# DrizzlingBytes.net
KiCad netlist of a schematic drawn in EAGLE
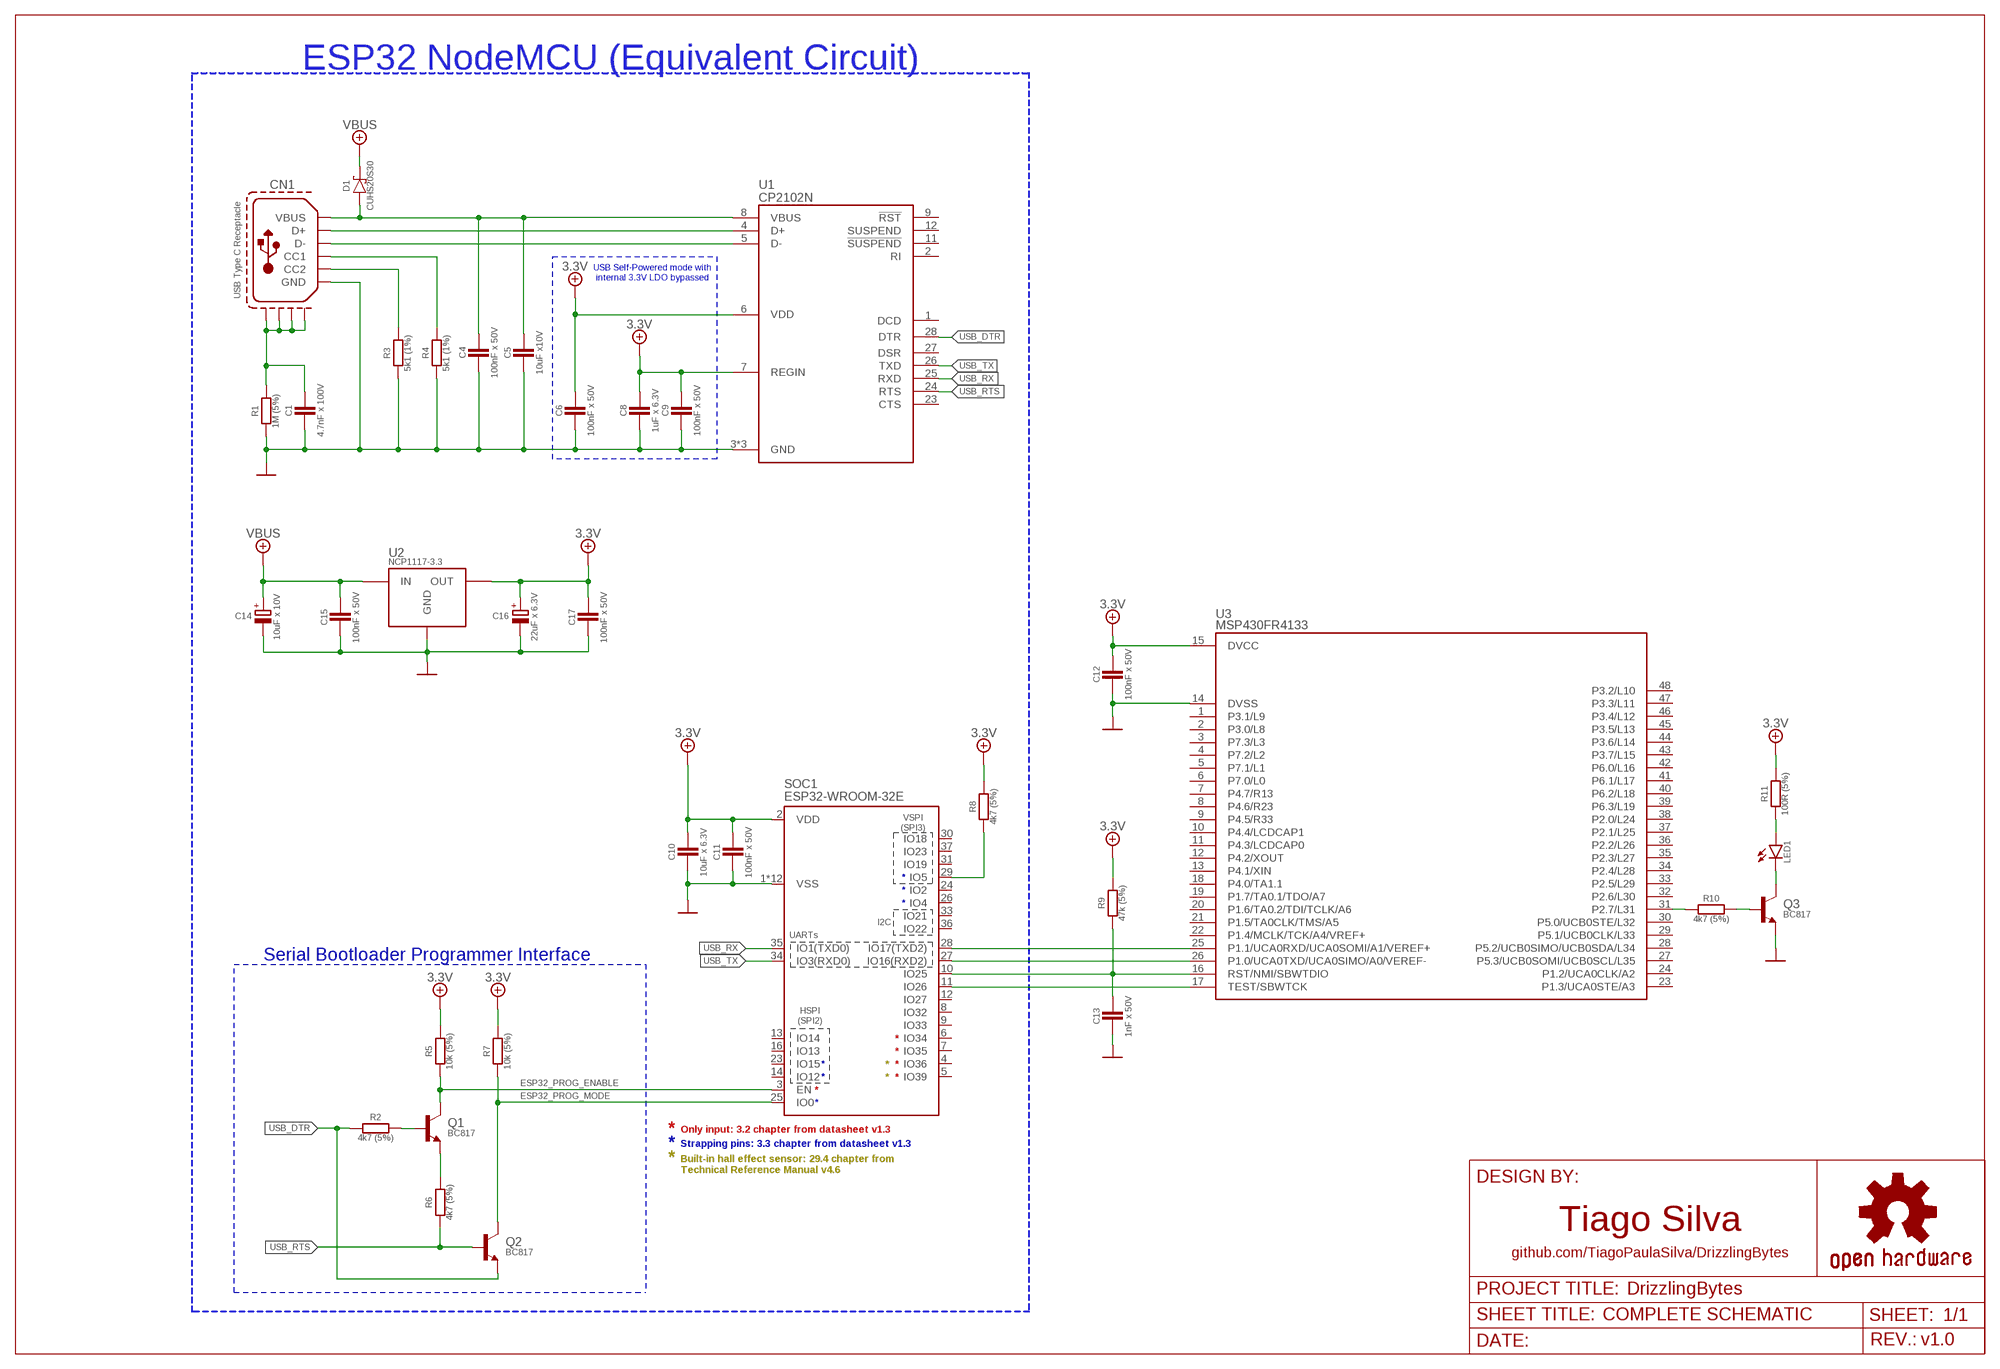
[diagram p0: schematic, sheet 1]

(export (version "E")
  (design (tool "Eeschema 10.0.6"))
  (components
    (comp (ref "C1")
      (value "4.7nF x 100V")
      (footprint "eagle-import:C0402")
      (libsource (lib "eagle-import") (part "C_0402"))
    )
    (comp (ref "C4")
      (value "100nF x 50V")
      (footprint "eagle-import:C0402")
      (libsource (lib "eagle-import") (part "C_0402"))
    )
    (comp (ref "C5")
      (value "10uF x10V")
      (footprint "eagle-import:C0402")
      (libsource (lib "eagle-import") (part "C_0402"))
    )
    (comp (ref "C6")
      (value "100nF x 50V")
      (footprint "eagle-import:C0402")
      (libsource (lib "eagle-import") (part "C_0402"))
    )
    (comp (ref "C8")
      (value "1uF x 6.3V")
      (footprint "eagle-import:C0402")
      (libsource (lib "eagle-import") (part "C_0402"))
    )
    (comp (ref "C9")
      (value "100nF x 50V")
      (footprint "eagle-import:C0402")
      (libsource (lib "eagle-import") (part "C_0402"))
    )
    (comp (ref "C10")
      (value "10uF x 6.3V")
      (footprint "eagle-import:C0402")
      (libsource (lib "eagle-import") (part "C_0402"))
    )
    (comp (ref "C11")
      (value "100nF x 50V")
      (footprint "eagle-import:C0402")
      (libsource (lib "eagle-import") (part "C_0402"))
    )
    (comp (ref "C12")
      (value "100nF x 50V")
      (footprint "eagle-import:C0402")
      (libsource (lib "eagle-import") (part "C_0402"))
    )
    (comp (ref "C13")
      (value "1nF x 50V")
      (footprint "eagle-import:C0402")
      (libsource (lib "eagle-import") (part "C_0402"))
    )
    (comp (ref "C14")
      (value "10uF x 10V")
      (footprint "eagle-import:C1206_POL")
      (description "Tantalum Electrolytic Capacitors (Low ESR)")
      (libsource (lib "eagle-import") (part "CP_1206_POL"))
    )
    (comp (ref "C15")
      (value "100nF x 50V")
      (footprint "eagle-import:C0402")
      (libsource (lib "eagle-import") (part "C_0402"))
    )
    (comp (ref "C16")
      (value "22uF x 6.3V")
      (footprint "eagle-import:C1206_POL")
      (description "Tantalum Electrolytic Capacitors (Low ESR)")
      (libsource (lib "eagle-import") (part "CP_1206_POL"))
    )
    (comp (ref "C17")
      (value "100nF x 50V")
      (footprint "eagle-import:C0402")
      (libsource (lib "eagle-import") (part "C_0402"))
    )
    (comp (ref "CN1")
      (value "USB Type C Receptacle")
      (footprint "eagle-import:USB-C-16P-2LAYER-PADS")
      (libsource (lib "eagle-import") (part "USB-C-16P-2LAYERS"))
    )
    (comp (ref "D1")
      (value "SCHOTTKY-CUHS20S30")
      (footprint "eagle-import:US2H-2")
      (fields (field (name "FAMILY") "CUHS20S30"))
      (libsource (lib "eagle-import") (part "SCHOTTKY-CUHS20S30"))
    )
    (comp (ref "LED1")
      (value "LED-0402")
      (footprint "eagle-import:LED-0402")
      (libsource (lib "eagle-import") (part "LED-0402"))
    )
    (comp (ref "Q1")
      (value "NPN-BC817")
      (footprint "eagle-import:SOT23-3")
      (fields (field (name "FAMILY") "BC817"))
      (libsource (lib "eagle-import") (part "NPN-BC817"))
    )
    (comp (ref "Q2")
      (value "NPN-BC817")
      (footprint "eagle-import:SOT23-3")
      (fields (field (name "FAMILY") "BC817"))
      (libsource (lib "eagle-import") (part "NPN-BC817"))
    )
    (comp (ref "Q3")
      (value "NPN-BC817")
      (footprint "eagle-import:SOT23-3")
      (fields (field (name "FAMILY") "BC817"))
      (libsource (lib "eagle-import") (part "NPN-BC817"))
    )
    (comp (ref "R1")
      (value "1M (5%)")
      (footprint "eagle-import:R0402")
      (libsource (lib "eagle-import") (part "R_0402"))
    )
    (comp (ref "R2")
      (value "4k7 (5%)")
      (footprint "eagle-import:R0402")
      (libsource (lib "eagle-import") (part "R_0402"))
    )
    (comp (ref "R3")
      (value "5k1 (1%)")
      (footprint "eagle-import:R0402")
      (libsource (lib "eagle-import") (part "R_0402"))
    )
    (comp (ref "R4")
      (value "5k1 (1%)")
      (footprint "eagle-import:R0402")
      (libsource (lib "eagle-import") (part "R_0402"))
    )
    (comp (ref "R5")
      (value "10k (5%)")
      (footprint "eagle-import:R0402")
      (libsource (lib "eagle-import") (part "R_0402"))
    )
    (comp (ref "R6")
      (value "4k7 (5%)")
      (footprint "eagle-import:R0402")
      (libsource (lib "eagle-import") (part "R_0402"))
    )
    (comp (ref "R7")
      (value "10k (5%)")
      (footprint "eagle-import:R0402")
      (libsource (lib "eagle-import") (part "R_0402"))
    )
    (comp (ref "R8")
      (value "4k7 (5%)")
      (footprint "eagle-import:R0402")
      (libsource (lib "eagle-import") (part "R_0402"))
    )
    (comp (ref "R9")
      (value "47k (5%)")
      (footprint "eagle-import:R0402")
      (libsource (lib "eagle-import") (part "R_0402"))
    )
    (comp (ref "R10")
      (value "4k7 (5%)")
      (footprint "eagle-import:R0402")
      (libsource (lib "eagle-import") (part "R_0402"))
    )
    (comp (ref "R11")
      (value "100R (5%)")
      (footprint "eagle-import:R0402")
      (libsource (lib "eagle-import") (part "R_0402"))
    )
    (comp (ref "SOC1")
      (value "ESP32-WROOM-32E")
      (footprint "eagle-import:ESP32-WROOM-32E")
      (libsource (lib "eagle-import") (part "ESP32-WROOM-32E-N4"))
    )
    (comp (ref "U1")
      (value "CP2102N")
      (footprint "eagle-import:QFN-28")
      (libsource (lib "eagle-import") (part "CP2102N"))
    )
    (comp (ref "U2")
      (value "1117-3.3V")
      (footprint "eagle-import:SOT-223-3")
      (fields (field (name "FAMILY") "LT1117-3.3") (field (name "FAMILY_1") "NCP1117-3.3"))
      (libsource (lib "eagle-import") (part "1117-3.3V"))
    )
    (comp (ref "U3")
      (value "MSP430FR4133")
      (footprint "eagle-import:TSSOP-48")
      (fields
        (field (name "MANUFACTURER_PART_NUMBER") "MSP430FR4133IG48R")
        (field (name "MOUSER_PART_NUMBER") "595-MSP430R4133IG48R")
      )
      (libsource (lib "eagle-import") (part "MSP430FR4133IG48R"))
    )
  )
  (nets
    (net (code "1") (name "/ESP32_PROG_ENABLE") (class "Default")
      (node (ref "Q1") (pin "3") (pinfunction "C_3") (pintype "passive"))
      (node (ref "R5") (pin "2") (pinfunction "2_2") (pintype "passive"))
      (node (ref "SOC1") (pin "3") (pinfunction "EN_3") (pintype "input"))
    )
    (net (code "2") (name "/ESP32_PROG_MODE") (class "Default")
      (node (ref "Q2") (pin "3") (pinfunction "C_3") (pintype "passive"))
      (node (ref "R7") (pin "2") (pinfunction "2_2") (pintype "passive"))
      (node (ref "SOC1") (pin "25") (pinfunction "IO0_25") (pintype "bidirectional"))
    )
    (net (code "3") (name "0V") (class "Default")
      (node (ref "C1") (pin "1") (pinfunction "1_1") (pintype "passive"))
      (node (ref "C10") (pin "2") (pinfunction "2_2") (pintype "passive"))
      (node (ref "C11") (pin "2") (pinfunction "2_2") (pintype "passive"))
      (node (ref "C12") (pin "1") (pinfunction "1_1") (pintype "passive"))
      (node (ref "C13") (pin "2") (pinfunction "2_2") (pintype "passive"))
      (node (ref "C14") (pin "2") (pinfunction "-_2") (pintype "passive"))
      (node (ref "C15") (pin "2") (pinfunction "2_2") (pintype "passive"))
      (node (ref "C16") (pin "2") (pinfunction "-_2") (pintype "passive"))
      (node (ref "C17") (pin "2") (pinfunction "2_2") (pintype "passive"))
      (node (ref "C4") (pin "1") (pinfunction "1_1") (pintype "passive"))
      (node (ref "C5") (pin "1") (pinfunction "1_1") (pintype "passive"))
      (node (ref "C6") (pin "1") (pinfunction "1_1") (pintype "passive"))
      (node (ref "C8") (pin "1") (pinfunction "1_1") (pintype "passive"))
      (node (ref "C9") (pin "1") (pinfunction "1_1") (pintype "passive"))
      (node (ref "CN1") (pin "GND") (pinfunction "GND_GND") (pintype "bidirectional"))
      (node (ref "CN1") (pin "GND2") (pinfunction "GND_GND2") (pintype "bidirectional"))
      (node (ref "Q3") (pin "2") (pinfunction "E_2") (pintype "passive"))
      (node (ref "R1") (pin "2") (pinfunction "2_2") (pintype "passive"))
      (node (ref "R3") (pin "2") (pinfunction "2_2") (pintype "passive"))
      (node (ref "R4") (pin "2") (pinfunction "2_2") (pintype "passive"))
      (node (ref "SOC1") (pin "1") (pinfunction "VSS_1") (pintype "power_in"))
      (node (ref "SOC1") (pin "15") (pinfunction "VSS_15") (pintype "power_in"))
      (node (ref "SOC1") (pin "38") (pinfunction "VSS_38") (pintype "power_in"))
      (node (ref "SOC1") (pin "E1") (pinfunction "VSS_E1") (pintype "power_in"))
      (node (ref "SOC1") (pin "E2") (pinfunction "VSS_E2") (pintype "power_in"))
      (node (ref "SOC1") (pin "E3") (pinfunction "VSS_E3") (pintype "power_in"))
      (node (ref "SOC1") (pin "E4") (pinfunction "VSS_E4") (pintype "power_in"))
      (node (ref "SOC1") (pin "E5") (pinfunction "VSS_E5") (pintype "power_in"))
      (node (ref "SOC1") (pin "E6") (pinfunction "VSS_E6") (pintype "power_in"))
      (node (ref "SOC1") (pin "E7") (pinfunction "VSS_E7") (pintype "power_in"))
      (node (ref "SOC1") (pin "E8") (pinfunction "VSS_E8") (pintype "power_in"))
      (node (ref "SOC1") (pin "E9") (pinfunction "VSS_E9") (pintype "power_in"))
      (node (ref "U1") (pin "3") (pinfunction "GND_3") (pintype "power_in"))
      (node (ref "U1") (pin "EXP") (pinfunction "GND_EXP") (pintype "power_in"))
      (node (ref "U1") (pin "M") (pinfunction "GND_M") (pintype "power_in"))
      (node (ref "U2") (pin "1") (pinfunction "GND_1") (pintype "bidirectional"))
      (node (ref "U3") (pin "14") (pinfunction "DVSS_14") (pintype "bidirectional"))
    )
    (net (code "4") (name "3.3V") (class "Default")
      (node (ref "C10") (pin "1") (pinfunction "1_1") (pintype "passive"))
      (node (ref "C11") (pin "1") (pinfunction "1_1") (pintype "passive"))
      (node (ref "C12") (pin "2") (pinfunction "2_2") (pintype "passive"))
      (node (ref "C16") (pin "1") (pinfunction "+_1") (pintype "passive"))
      (node (ref "C17") (pin "1") (pinfunction "1_1") (pintype "passive"))
      (node (ref "C6") (pin "2") (pinfunction "2_2") (pintype "passive"))
      (node (ref "C8") (pin "2") (pinfunction "2_2") (pintype "passive"))
      (node (ref "C9") (pin "2") (pinfunction "2_2") (pintype "passive"))
      (node (ref "R11") (pin "2") (pinfunction "2_2") (pintype "passive"))
      (node (ref "R5") (pin "1") (pinfunction "1_1") (pintype "passive"))
      (node (ref "R7") (pin "1") (pinfunction "1_1") (pintype "passive"))
      (node (ref "R8") (pin "2") (pinfunction "2_2") (pintype "passive"))
      (node (ref "R9") (pin "2") (pinfunction "2_2") (pintype "passive"))
      (node (ref "SOC1") (pin "2") (pinfunction "VDD_2") (pintype "power_in"))
      (node (ref "U1") (pin "6") (pinfunction "VDD_6") (pintype "power_in"))
      (node (ref "U1") (pin "7") (pinfunction "REGIN_7") (pintype "passive"))
      (node (ref "U2") (pin "2") (pinfunction "OUT_2") (pintype "bidirectional"))
      (node (ref "U2") (pin "4") (pinfunction "OUT_4") (pintype "bidirectional"))
      (node (ref "U3") (pin "15") (pinfunction "DVCC_15") (pintype "bidirectional"))
    )
    (net (code "5") (name "Net-(CN1-CC1)") (class "Default")
      (node (ref "CN1") (pin "A5") (pinfunction "CC1_A5") (pintype "bidirectional"))
      (node (ref "R4") (pin "1") (pinfunction "1_1") (pintype "passive"))
    )
    (net (code "6") (name "Net-(CN1-CC2)") (class "Default")
      (node (ref "CN1") (pin "B5") (pinfunction "CC2_B5") (pintype "bidirectional"))
      (node (ref "R3") (pin "1") (pinfunction "1_1") (pintype "passive"))
    )
    (net (code "7") (name "Net-(CN1-S1)") (class "Default")
      (node (ref "C1") (pin "2") (pinfunction "2_2") (pintype "passive"))
      (node (ref "CN1") (pin "SHLD1") (pinfunction "S1_SHLD1") (pintype "passive"))
      (node (ref "CN1") (pin "SHLD2") (pinfunction "S2_SHLD2") (pintype "passive"))
      (node (ref "CN1") (pin "SHLD3") (pinfunction "S3_SHLD3") (pintype "passive"))
      (node (ref "CN1") (pin "SHLD4") (pinfunction "S4_SHLD4") (pintype "passive"))
      (node (ref "R1") (pin "1") (pinfunction "1_1") (pintype "passive"))
    )
    (net (code "8") (name "Net-(D1-A)") (class "Default")
      (node (ref "C4") (pin "2") (pinfunction "2_2") (pintype "passive"))
      (node (ref "C5") (pin "2") (pinfunction "2_2") (pintype "passive"))
      (node (ref "CN1") (pin "VBUS1") (pinfunction "VBUS_VBUS1") (pintype "bidirectional"))
      (node (ref "CN1") (pin "VBUS2") (pinfunction "VBUS_VBUS2") (pintype "bidirectional"))
      (node (ref "D1") (pin "2") (pinfunction "A_2") (pintype "passive"))
      (node (ref "U1") (pin "8") (pinfunction "VBUS_8") (pintype "passive"))
    )
    (net (code "9") (name "Net-(LED1-A)") (class "Default")
      (node (ref "LED1") (pin "2") (pinfunction "A_2") (pintype "passive"))
      (node (ref "R11") (pin "1") (pinfunction "1_1") (pintype "passive"))
    )
    (net (code "10") (name "Net-(LED1-K)") (class "Default")
      (node (ref "LED1") (pin "1") (pinfunction "K_1") (pintype "passive"))
      (node (ref "Q3") (pin "3") (pinfunction "C_3") (pintype "passive"))
    )
    (net (code "11") (name "Net-(Q1-B)") (class "Default")
      (node (ref "Q1") (pin "1") (pinfunction "B_1") (pintype "passive"))
      (node (ref "R2") (pin "1") (pinfunction "1_1") (pintype "passive"))
    )
    (net (code "12") (name "Net-(Q3-B)") (class "Default")
      (node (ref "Q3") (pin "1") (pinfunction "B_1") (pintype "passive"))
      (node (ref "R10") (pin "2") (pinfunction "2_2") (pintype "passive"))
    )
    (net (code "13") (name "Net-(SOC1-IO5)") (class "Default")
      (node (ref "R8") (pin "1") (pinfunction "1_1") (pintype "passive"))
      (node (ref "SOC1") (pin "29") (pinfunction "IO5_29") (pintype "bidirectional"))
    )
    (net (code "14") (name "Net-(SOC1-IO16(RXD2))") (class "Default")
      (node (ref "SOC1") (pin "27") (pinfunction "IO16(RXD2)_27") (pintype "bidirectional"))
      (node (ref "U3") (pin "26") (pinfunction "P1.0/UCA0TXD/UCA0SIMO/A0/VEREF-_26") (pintype "bidirectional"))
    )
    (net (code "15") (name "Net-(SOC1-IO17(TXD2))") (class "Default")
      (node (ref "SOC1") (pin "28") (pinfunction "IO17(TXD2)_28") (pintype "bidirectional"))
      (node (ref "U3") (pin "25") (pinfunction "P1.1/UCA0RXD/UCA0SOMI/A1/VEREF+_25") (pintype "bidirectional"))
    )
    (net (code "16") (name "Net-(SOC1-IO25)") (class "Default")
      (node (ref "C13") (pin "1") (pinfunction "1_1") (pintype "passive"))
      (node (ref "R9") (pin "1") (pinfunction "1_1") (pintype "passive"))
      (node (ref "SOC1") (pin "10") (pinfunction "IO25_10") (pintype "bidirectional"))
      (node (ref "U3") (pin "16") (pinfunction "RST/NMI/SBWTDIO_16") (pintype "bidirectional"))
    )
    (net (code "17") (name "Net-(SOC1-IO26)") (class "Default")
      (node (ref "SOC1") (pin "11") (pinfunction "IO26_11") (pintype "bidirectional"))
      (node (ref "U3") (pin "17") (pinfunction "TEST/SBWTCK_17") (pintype "bidirectional"))
    )
    (net (code "18") (name "Net-(U1-D+)") (class "Default")
      (node (ref "CN1") (pin "A6") (pinfunction "D+_A6") (pintype "bidirectional"))
      (node (ref "CN1") (pin "B6") (pinfunction "D+_B6") (pintype "bidirectional"))
      (node (ref "U1") (pin "4") (pinfunction "D+_4") (pintype "bidirectional"))
    )
    (net (code "19") (name "Net-(U1-D-)") (class "Default")
      (node (ref "CN1") (pin "A7") (pinfunction "D-_A7") (pintype "bidirectional"))
      (node (ref "CN1") (pin "B7") (pinfunction "D-_B7") (pintype "bidirectional"))
      (node (ref "U1") (pin "5") (pinfunction "D-_5") (pintype "bidirectional"))
    )
    (net (code "20") (name "Net-(U3-P2.7{slash}L31)") (class "Default")
      (node (ref "R10") (pin "1") (pinfunction "1_1") (pintype "passive"))
      (node (ref "U3") (pin "31") (pinfunction "P2.7/L31_31") (pintype "bidirectional"))
    )
    (net (code "21") (name "USB_DTR") (class "Default")
      (node (ref "Q2") (pin "2") (pinfunction "E_2") (pintype "passive"))
      (node (ref "R2") (pin "2") (pinfunction "2_2") (pintype "passive"))
      (node (ref "U1") (pin "28") (pinfunction "DTR_28") (pintype "output"))
    )
    (net (code "22") (name "USB_RTS") (class "Default")
      (node (ref "Q1") (pin "2") (pinfunction "E_2") (pintype "passive"))
      (node (ref "Q2") (pin "1") (pinfunction "B_1") (pintype "passive"))
      (node (ref "R6") (pin "1") (pinfunction "1_1") (pintype "passive"))
      (node (ref "R6") (pin "2") (pinfunction "2_2") (pintype "passive"))
      (node (ref "U1") (pin "24") (pinfunction "RTS_24") (pintype "output"))
    )
    (net (code "23") (name "USB_RX") (class "Default")
      (node (ref "SOC1") (pin "35") (pinfunction "IO1(TXD0)_35") (pintype "bidirectional"))
      (node (ref "U1") (pin "25") (pinfunction "RXD_25") (pintype "input"))
    )
    (net (code "24") (name "USB_TX") (class "Default")
      (node (ref "SOC1") (pin "34") (pinfunction "IO3(RXD0)_34") (pintype "bidirectional"))
      (node (ref "U1") (pin "26") (pinfunction "TXD_26") (pintype "output"))
    )
    (net (code "25") (name "VBUS") (class "Default")
      (node (ref "C14") (pin "1") (pinfunction "+_1") (pintype "passive"))
      (node (ref "C15") (pin "1") (pinfunction "1_1") (pintype "passive"))
      (node (ref "D1") (pin "1") (pinfunction "K_1") (pintype "passive"))
      (node (ref "U2") (pin "3") (pinfunction "IN_3") (pintype "bidirectional"))
    )
    (net (code "26") (name "unconnected-(SOC1-IO2-Pad24)") (class "Default")
      (node (ref "SOC1") (pin "24") (pinfunction "IO2_24") (pintype "bidirectional"))
    )
    (net (code "27") (name "unconnected-(SOC1-IO4-Pad26)") (class "Default")
      (node (ref "SOC1") (pin "26") (pinfunction "IO4_26") (pintype "bidirectional"))
    )
    (net (code "28") (name "unconnected-(SOC1-IO12-Pad14)") (class "Default")
      (node (ref "SOC1") (pin "14") (pinfunction "IO12_14") (pintype "bidirectional"))
    )
    (net (code "29") (name "unconnected-(SOC1-IO13-Pad16)") (class "Default")
      (node (ref "SOC1") (pin "16") (pinfunction "IO13_16") (pintype "bidirectional"))
    )
    (net (code "30") (name "unconnected-(SOC1-IO14-Pad13)") (class "Default")
      (node (ref "SOC1") (pin "13") (pinfunction "IO14_13") (pintype "bidirectional"))
    )
    (net (code "31") (name "unconnected-(SOC1-IO15-Pad23)") (class "Default")
      (node (ref "SOC1") (pin "23") (pinfunction "IO15_23") (pintype "bidirectional"))
    )
    (net (code "32") (name "unconnected-(SOC1-IO18-Pad30)") (class "Default")
      (node (ref "SOC1") (pin "30") (pinfunction "IO18_30") (pintype "bidirectional"))
    )
    (net (code "33") (name "unconnected-(SOC1-IO19-Pad31)") (class "Default")
      (node (ref "SOC1") (pin "31") (pinfunction "IO19_31") (pintype "bidirectional"))
    )
    (net (code "34") (name "unconnected-(SOC1-IO21-Pad33)") (class "Default")
      (node (ref "SOC1") (pin "33") (pinfunction "IO21_33") (pintype "bidirectional"))
    )
    (net (code "35") (name "unconnected-(SOC1-IO22-Pad36)") (class "Default")
      (node (ref "SOC1") (pin "36") (pinfunction "IO22_36") (pintype "bidirectional"))
    )
    (net (code "36") (name "unconnected-(SOC1-IO23-Pad37)") (class "Default")
      (node (ref "SOC1") (pin "37") (pinfunction "IO23_37") (pintype "bidirectional"))
    )
    (net (code "37") (name "unconnected-(SOC1-IO27-Pad12)") (class "Default")
      (node (ref "SOC1") (pin "12") (pinfunction "IO27_12") (pintype "bidirectional"))
    )
    (net (code "38") (name "unconnected-(SOC1-IO32-Pad8)") (class "Default")
      (node (ref "SOC1") (pin "8") (pinfunction "IO32_8") (pintype "bidirectional"))
    )
    (net (code "39") (name "unconnected-(SOC1-IO33-Pad9)") (class "Default")
      (node (ref "SOC1") (pin "9") (pinfunction "IO33_9") (pintype "bidirectional"))
    )
    (net (code "40") (name "unconnected-(SOC1-IO34-Pad6)") (class "Default")
      (node (ref "SOC1") (pin "6") (pinfunction "IO34_6") (pintype "bidirectional"))
    )
    (net (code "41") (name "unconnected-(SOC1-IO35-Pad7)") (class "Default")
      (node (ref "SOC1") (pin "7") (pinfunction "IO35_7") (pintype "bidirectional"))
    )
    (net (code "42") (name "unconnected-(SOC1-IO36-Pad4)") (class "Default")
      (node (ref "SOC1") (pin "4") (pinfunction "IO36_4") (pintype "bidirectional"))
    )
    (net (code "43") (name "unconnected-(SOC1-IO39-Pad5)") (class "Default")
      (node (ref "SOC1") (pin "5") (pinfunction "IO39_5") (pintype "bidirectional"))
    )
    (net (code "44") (name "unconnected-(U1-CTS-Pad23)") (class "Default")
      (node (ref "U1") (pin "23") (pinfunction "CTS_23") (pintype "passive"))
    )
    (net (code "45") (name "unconnected-(U1-DCD-Pad1)") (class "Default")
      (node (ref "U1") (pin "1") (pinfunction "DCD_1") (pintype "passive"))
    )
    (net (code "46") (name "unconnected-(U1-DSR-Pad27)") (class "Default")
      (node (ref "U1") (pin "27") (pinfunction "DSR_27") (pintype "passive"))
    )
    (net (code "47") (name "unconnected-(U1-RI-Pad2)") (class "Default")
      (node (ref "U1") (pin "2") (pinfunction "RI_2") (pintype "passive"))
    )
    (net (code "48") (name "unconnected-(U1-SUSPEND-Pad12)") (class "Default")
      (node (ref "U1") (pin "12") (pinfunction "SUSPEND_12") (pintype "passive"))
    )
    (net (code "49") (name "unconnected-(U1-~{RST}-Pad9)") (class "Default")
      (node (ref "U1") (pin "9") (pinfunction "~{RST}_9") (pintype "bidirectional"))
    )
    (net (code "50") (name "unconnected-(U1-~{SUSPEND}-Pad11)") (class "Default")
      (node (ref "U1") (pin "11") (pinfunction "~{SUSPEND}_11") (pintype "output"))
    )
    (net (code "51") (name "unconnected-(U3-P1.2{slash}UCA0CLK{slash}A2-Pad24)") (class "Default")
      (node (ref "U3") (pin "24") (pinfunction "P1.2/UCA0CLK/A2_24") (pintype "bidirectional"))
    )
    (net (code "52") (name "unconnected-(U3-P1.3{slash}UCA0STE{slash}A3-Pad23)") (class "Default")
      (node (ref "U3") (pin "23") (pinfunction "P1.3/UCA0STE/A3_23") (pintype "bidirectional"))
    )
    (net (code "53") (name "unconnected-(U3-P1.4{slash}MCLK{slash}TCK{slash}A4{slash}VREF+-Pad22)") (class "Default")
      (node (ref "U3") (pin "22") (pinfunction "P1.4/MCLK/TCK/A4/VREF+_22") (pintype "bidirectional"))
    )
    (net (code "54") (name "unconnected-(U3-P1.5{slash}TA0CLK{slash}TMS{slash}A5-Pad21)") (class "Default")
      (node (ref "U3") (pin "21") (pinfunction "P1.5/TA0CLK/TMS/A5_21") (pintype "bidirectional"))
    )
    (net (code "55") (name "unconnected-(U3-P1.6{slash}TA0.2{slash}TDI{slash}TCLK{slash}A6-Pad20)") (class "Default")
      (node (ref "U3") (pin "20") (pinfunction "P1.6/TA0.2/TDI/TCLK/A6_20") (pintype "bidirectional"))
    )
    (net (code "56") (name "unconnected-(U3-P1.7{slash}TA0.1{slash}TDO{slash}A7-Pad19)") (class "Default")
      (node (ref "U3") (pin "19") (pinfunction "P1.7/TA0.1/TDO/A7_19") (pintype "bidirectional"))
    )
    (net (code "57") (name "unconnected-(U3-P2.0{slash}L24-Pad38)") (class "Default")
      (node (ref "U3") (pin "38") (pinfunction "P2.0/L24_38") (pintype "bidirectional"))
    )
    (net (code "58") (name "unconnected-(U3-P2.1{slash}L25-Pad37)") (class "Default")
      (node (ref "U3") (pin "37") (pinfunction "P2.1/L25_37") (pintype "bidirectional"))
    )
    (net (code "59") (name "unconnected-(U3-P2.2{slash}L26-Pad36)") (class "Default")
      (node (ref "U3") (pin "36") (pinfunction "P2.2/L26_36") (pintype "bidirectional"))
    )
    (net (code "60") (name "unconnected-(U3-P2.3{slash}L27-Pad35)") (class "Default")
      (node (ref "U3") (pin "35") (pinfunction "P2.3/L27_35") (pintype "bidirectional"))
    )
    (net (code "61") (name "unconnected-(U3-P2.4{slash}L28-Pad34)") (class "Default")
      (node (ref "U3") (pin "34") (pinfunction "P2.4/L28_34") (pintype "bidirectional"))
    )
    (net (code "62") (name "unconnected-(U3-P2.5{slash}L29-Pad33)") (class "Default")
      (node (ref "U3") (pin "33") (pinfunction "P2.5/L29_33") (pintype "bidirectional"))
    )
    (net (code "63") (name "unconnected-(U3-P2.6{slash}L30-Pad32)") (class "Default")
      (node (ref "U3") (pin "32") (pinfunction "P2.6/L30_32") (pintype "bidirectional"))
    )
    (net (code "64") (name "unconnected-(U3-P3.0{slash}L8-Pad2)") (class "Default")
      (node (ref "U3") (pin "2") (pinfunction "P3.0/L8_2") (pintype "bidirectional"))
    )
    (net (code "65") (name "unconnected-(U3-P3.1{slash}L9-Pad1)") (class "Default")
      (node (ref "U3") (pin "1") (pinfunction "P3.1/L9_1") (pintype "bidirectional"))
    )
    (net (code "66") (name "unconnected-(U3-P3.2{slash}L10-Pad48)") (class "Default")
      (node (ref "U3") (pin "48") (pinfunction "P3.2/L10_48") (pintype "bidirectional"))
    )
    (net (code "67") (name "unconnected-(U3-P3.3{slash}L11-Pad47)") (class "Default")
      (node (ref "U3") (pin "47") (pinfunction "P3.3/L11_47") (pintype "bidirectional"))
    )
    (net (code "68") (name "unconnected-(U3-P3.4{slash}L12-Pad46)") (class "Default")
      (node (ref "U3") (pin "46") (pinfunction "P3.4/L12_46") (pintype "bidirectional"))
    )
    (net (code "69") (name "unconnected-(U3-P3.5{slash}L13-Pad45)") (class "Default")
      (node (ref "U3") (pin "45") (pinfunction "P3.5/L13_45") (pintype "bidirectional"))
    )
    (net (code "70") (name "unconnected-(U3-P3.6{slash}L14-Pad44)") (class "Default")
      (node (ref "U3") (pin "44") (pinfunction "P3.6/L14_44") (pintype "bidirectional"))
    )
    (net (code "71") (name "unconnected-(U3-P3.7{slash}L15-Pad43)") (class "Default")
      (node (ref "U3") (pin "43") (pinfunction "P3.7/L15_43") (pintype "bidirectional"))
    )
    (net (code "72") (name "unconnected-(U3-P4.0{slash}TA1.1-Pad18)") (class "Default")
      (node (ref "U3") (pin "18") (pinfunction "P4.0/TA1.1_18") (pintype "bidirectional"))
    )
    (net (code "73") (name "unconnected-(U3-P4.1{slash}XIN-Pad13)") (class "Default")
      (node (ref "U3") (pin "13") (pinfunction "P4.1/XIN_13") (pintype "bidirectional"))
    )
    (net (code "74") (name "unconnected-(U3-P4.2{slash}XOUT-Pad12)") (class "Default")
      (node (ref "U3") (pin "12") (pinfunction "P4.2/XOUT_12") (pintype "bidirectional"))
    )
    (net (code "75") (name "unconnected-(U3-P4.3{slash}LCDCAP0-Pad11)") (class "Default")
      (node (ref "U3") (pin "11") (pinfunction "P4.3/LCDCAP0_11") (pintype "bidirectional"))
    )
    (net (code "76") (name "unconnected-(U3-P4.4{slash}LCDCAP1-Pad10)") (class "Default")
      (node (ref "U3") (pin "10") (pinfunction "P4.4/LCDCAP1_10") (pintype "bidirectional"))
    )
    (net (code "77") (name "unconnected-(U3-P4.5{slash}R33-Pad9)") (class "Default")
      (node (ref "U3") (pin "9") (pinfunction "P4.5/R33_9") (pintype "bidirectional"))
    )
    (net (code "78") (name "unconnected-(U3-P4.6{slash}R23-Pad8)") (class "Default")
      (node (ref "U3") (pin "8") (pinfunction "P4.6/R23_8") (pintype "bidirectional"))
    )
    (net (code "79") (name "unconnected-(U3-P4.7{slash}R13-Pad7)") (class "Default")
      (node (ref "U3") (pin "7") (pinfunction "P4.7/R13_7") (pintype "bidirectional"))
    )
    (net (code "80") (name "unconnected-(U3-P5.0{slash}UCB0STE{slash}L32-Pad30)") (class "Default")
      (node (ref "U3") (pin "30") (pinfunction "P5.0/UCB0STE/L32_30") (pintype "bidirectional"))
    )
    (net (code "81") (name "unconnected-(U3-P5.1{slash}UCB0CLK{slash}L33-Pad29)") (class "Default")
      (node (ref "U3") (pin "29") (pinfunction "P5.1/UCB0CLK/L33_29") (pintype "bidirectional"))
    )
    (net (code "82") (name "unconnected-(U3-P5.2{slash}UCB0SIMO{slash}UCB0SDA{slash}L34-Pad28)") (class "Default")
      (node (ref "U3") (pin "28") (pinfunction "P5.2/UCB0SIMO/UCB0SDA/L34_28") (pintype "bidirectional"))
    )
    (net (code "83") (name "unconnected-(U3-P5.3{slash}UCB0SOMI{slash}UCB0SCL{slash}L35-Pad27)") (class "Default")
      (node (ref "U3") (pin "27") (pinfunction "P5.3/UCB0SOMI/UCB0SCL/L35_27") (pintype "bidirectional"))
    )
    (net (code "84") (name "unconnected-(U3-P6.0{slash}L16-Pad42)") (class "Default")
      (node (ref "U3") (pin "42") (pinfunction "P6.0/L16_42") (pintype "bidirectional"))
    )
    (net (code "85") (name "unconnected-(U3-P6.1{slash}L17-Pad41)") (class "Default")
      (node (ref "U3") (pin "41") (pinfunction "P6.1/L17_41") (pintype "bidirectional"))
    )
    (net (code "86") (name "unconnected-(U3-P6.2{slash}L18-Pad40)") (class "Default")
      (node (ref "U3") (pin "40") (pinfunction "P6.2/L18_40") (pintype "bidirectional"))
    )
    (net (code "87") (name "unconnected-(U3-P6.3{slash}L19-Pad39)") (class "Default")
      (node (ref "U3") (pin "39") (pinfunction "P6.3/L19_39") (pintype "bidirectional"))
    )
    (net (code "88") (name "unconnected-(U3-P7.0{slash}L0-Pad6)") (class "Default")
      (node (ref "U3") (pin "6") (pinfunction "P7.0/L0_6") (pintype "bidirectional"))
    )
    (net (code "89") (name "unconnected-(U3-P7.1{slash}L1-Pad5)") (class "Default")
      (node (ref "U3") (pin "5") (pinfunction "P7.1/L1_5") (pintype "bidirectional"))
    )
    (net (code "90") (name "unconnected-(U3-P7.2{slash}L2-Pad4)") (class "Default")
      (node (ref "U3") (pin "4") (pinfunction "P7.2/L2_4") (pintype "bidirectional"))
    )
    (net (code "91") (name "unconnected-(U3-P7.3{slash}L3-Pad3)") (class "Default")
      (node (ref "U3") (pin "3") (pinfunction "P7.3/L3_3") (pintype "bidirectional"))
    )
  )
)
